# PaPArray_full.net
KiCad netlist of a schematic drawn in EAGLE
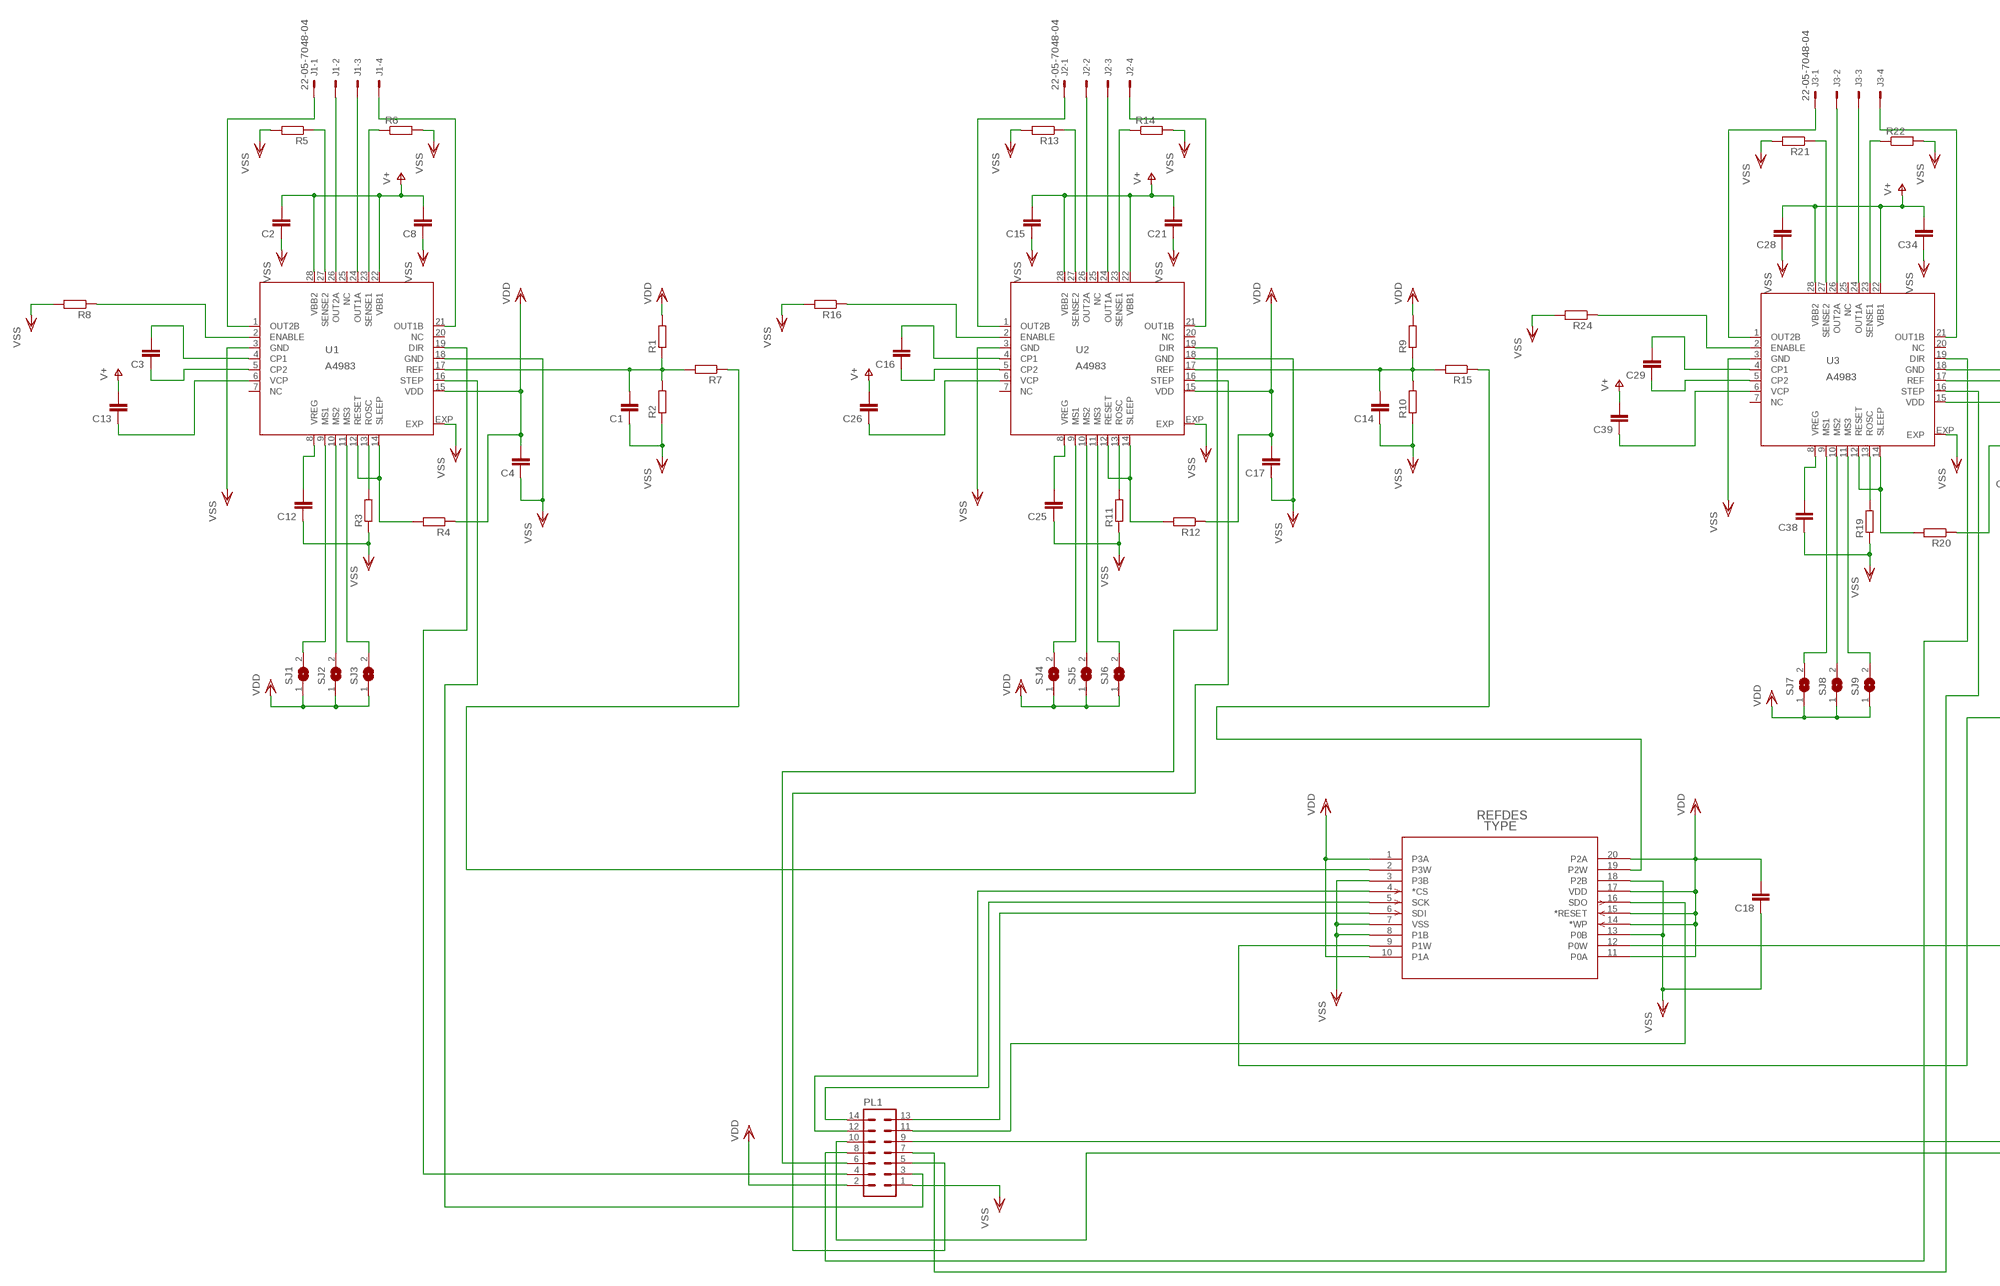
[diagram p0: schematic, sheet 1, part 1 of 2]
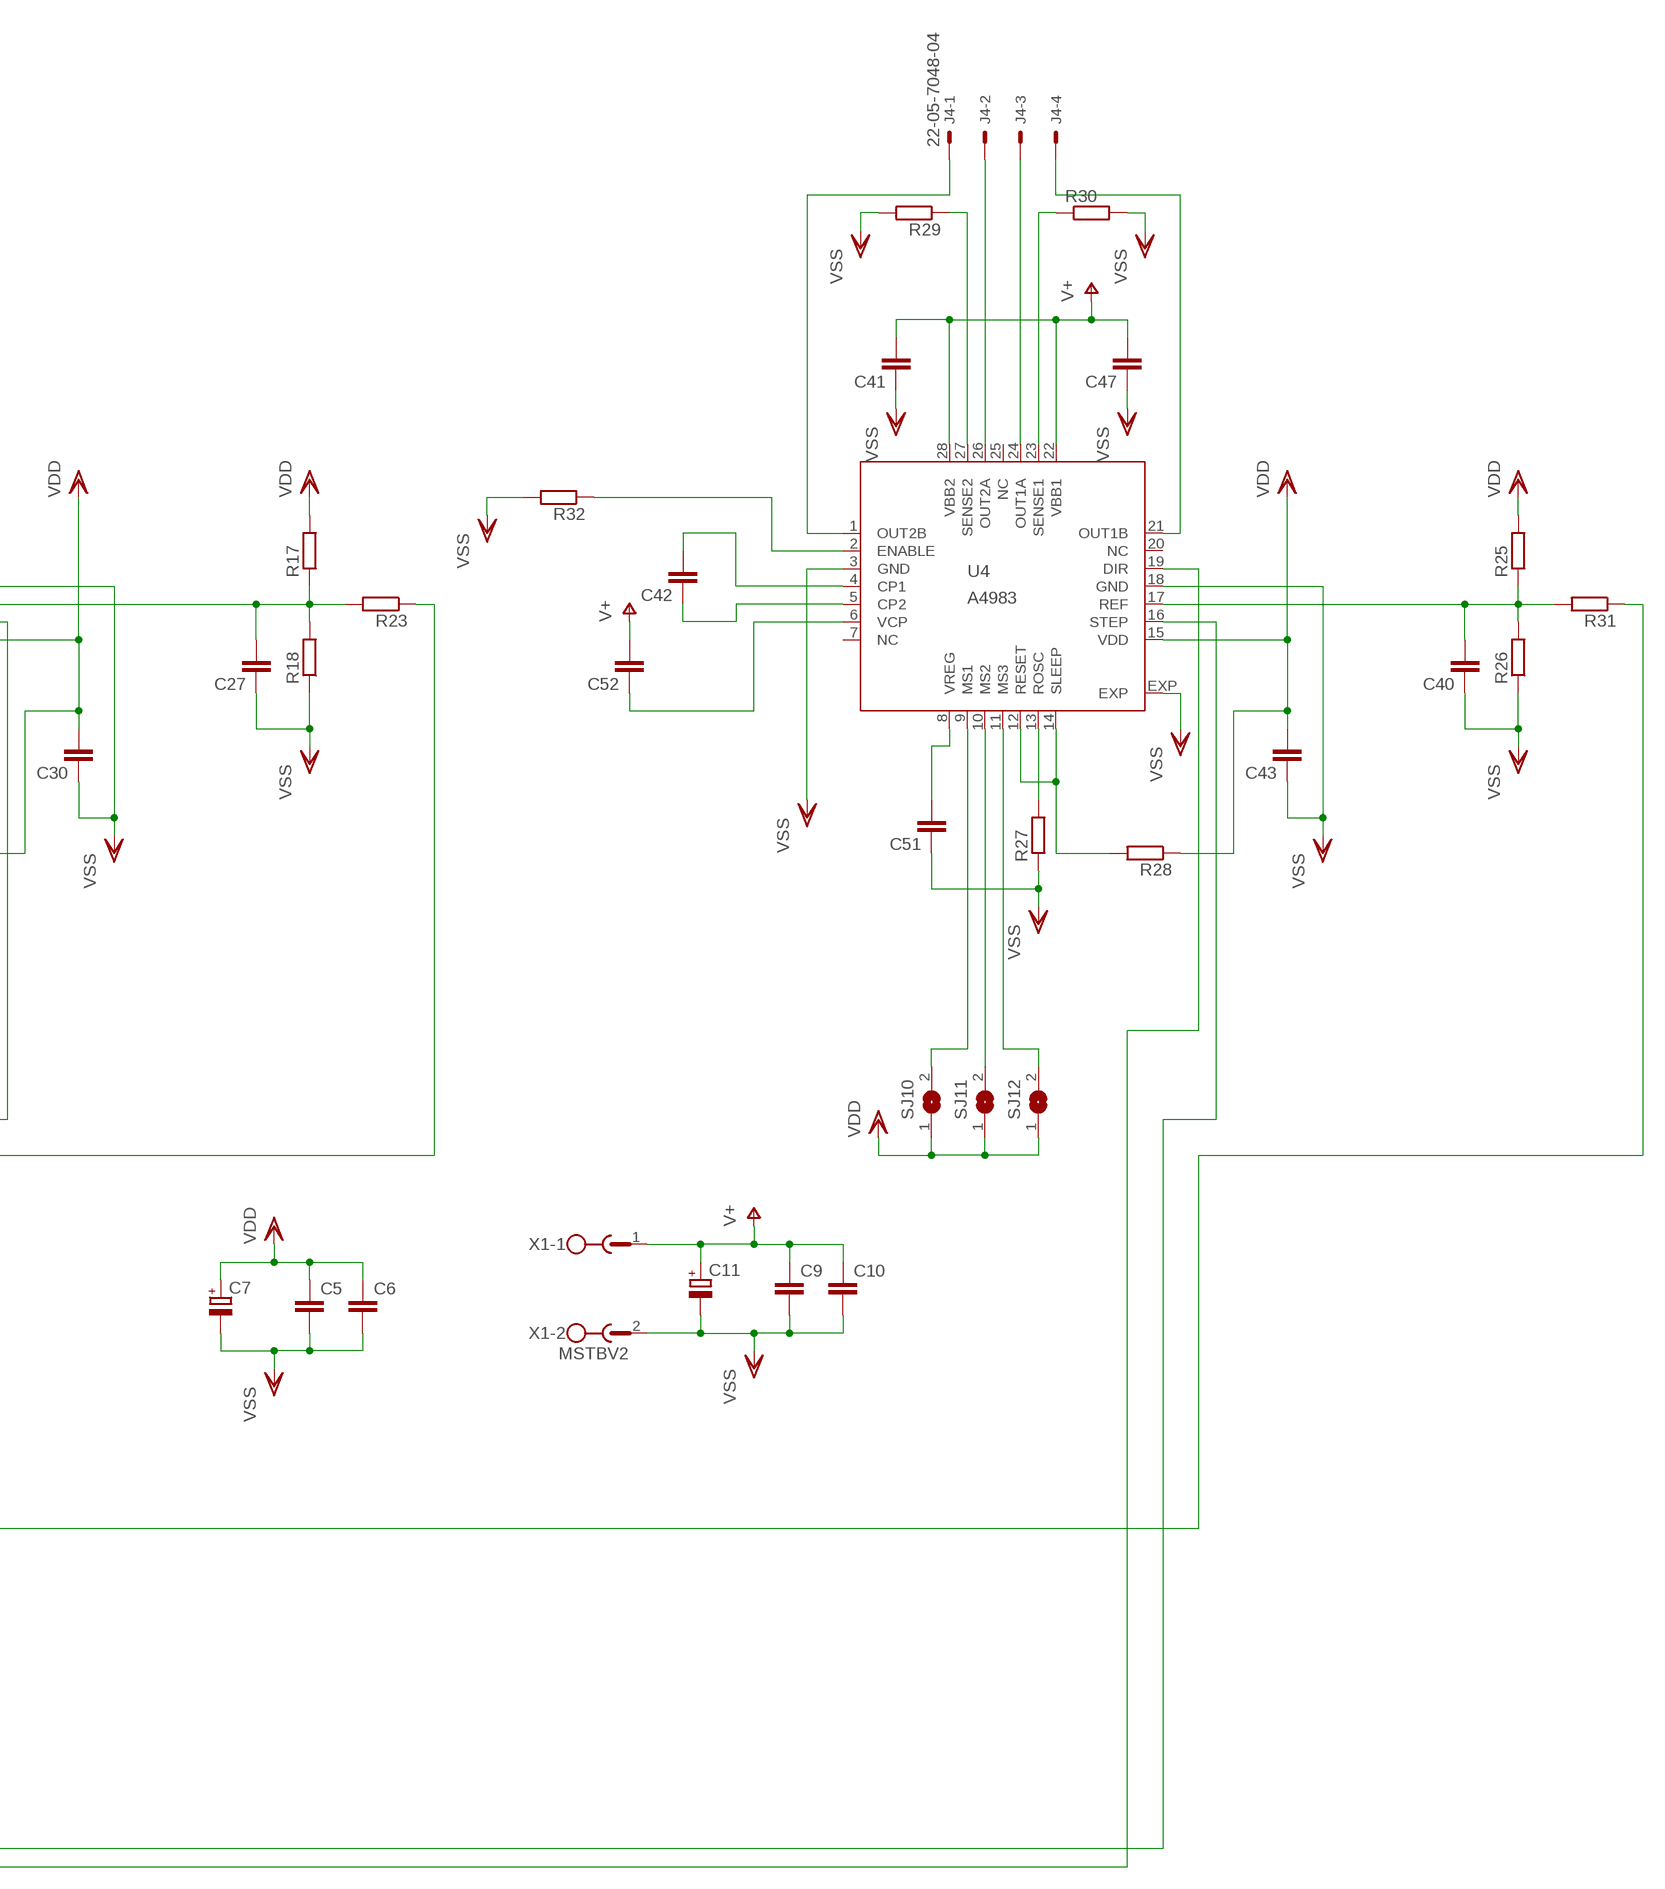
[diagram p1: schematic, sheet 1, part 2 of 2]

(export (version "E")
  (design (tool "Eeschema 10.0.6"))
  (components
    (comp (ref "C1")
      (value "C-EUC0603")
      (footprint "eagle-import:C0603")
      (libsource (lib "eagle-import") (part "C-EUC0603"))
    )
    (comp (ref "C2")
      (value "C-EUC0603")
      (footprint "eagle-import:C0603")
      (libsource (lib "eagle-import") (part "C-EUC0603"))
    )
    (comp (ref "C3")
      (value "C-EUC0603")
      (footprint "eagle-import:C0603")
      (libsource (lib "eagle-import") (part "C-EUC0603"))
    )
    (comp (ref "C4")
      (value "C-EUC0603")
      (footprint "eagle-import:C0603")
      (libsource (lib "eagle-import") (part "C-EUC0603"))
    )
    (comp (ref "C5")
      (value "C-EUC0603")
      (footprint "eagle-import:C0603")
      (libsource (lib "eagle-import") (part "C-EUC0603"))
    )
    (comp (ref "C6")
      (value "C-EUC0603")
      (footprint "eagle-import:C0603")
      (libsource (lib "eagle-import") (part "C-EUC0603"))
    )
    (comp (ref "C7")
      (value "CPOL-EUE5-5")
      (footprint "eagle-import:E5-5")
      (libsource (lib "eagle-import") (part "CPOL-EUE5-5"))
    )
    (comp (ref "C8")
      (value "C-EUC0603")
      (footprint "eagle-import:C0603")
      (libsource (lib "eagle-import") (part "C-EUC0603"))
    )
    (comp (ref "C9")
      (value "C-EUC0603")
      (footprint "eagle-import:C0603")
      (libsource (lib "eagle-import") (part "C-EUC0603"))
    )
    (comp (ref "C10")
      (value "C-EUC0603")
      (footprint "eagle-import:C0603")
      (libsource (lib "eagle-import") (part "C-EUC0603"))
    )
    (comp (ref "C11")
      (value "CPOL-EUE5-5")
      (footprint "eagle-import:E5-5")
      (libsource (lib "eagle-import") (part "CPOL-EUE5-5"))
    )
    (comp (ref "C12")
      (value "C-EUC0603")
      (footprint "eagle-import:C0603")
      (libsource (lib "eagle-import") (part "C-EUC0603"))
    )
    (comp (ref "C13")
      (value "C-EUC0603")
      (footprint "eagle-import:C0603")
      (libsource (lib "eagle-import") (part "C-EUC0603"))
    )
    (comp (ref "C14")
      (value "C-EUC0603")
      (footprint "eagle-import:C0603")
      (libsource (lib "eagle-import") (part "C-EUC0603"))
    )
    (comp (ref "C15")
      (value "C-EUC0603")
      (footprint "eagle-import:C0603")
      (libsource (lib "eagle-import") (part "C-EUC0603"))
    )
    (comp (ref "C16")
      (value "C-EUC0603")
      (footprint "eagle-import:C0603")
      (libsource (lib "eagle-import") (part "C-EUC0603"))
    )
    (comp (ref "C17")
      (value "C-EUC0603")
      (footprint "eagle-import:C0603")
      (libsource (lib "eagle-import") (part "C-EUC0603"))
    )
    (comp (ref "C18")
      (value "C-EUC0603")
      (footprint "eagle-import:C0603")
      (libsource (lib "eagle-import") (part "C-EUC0603"))
    )
    (comp (ref "C21")
      (value "C-EUC0603")
      (footprint "eagle-import:C0603")
      (libsource (lib "eagle-import") (part "C-EUC0603"))
    )
    (comp (ref "C25")
      (value "C-EUC0603")
      (footprint "eagle-import:C0603")
      (libsource (lib "eagle-import") (part "C-EUC0603"))
    )
    (comp (ref "C26")
      (value "C-EUC0603")
      (footprint "eagle-import:C0603")
      (libsource (lib "eagle-import") (part "C-EUC0603"))
    )
    (comp (ref "C27")
      (value "C-EUC0603")
      (footprint "eagle-import:C0603")
      (libsource (lib "eagle-import") (part "C-EUC0603"))
    )
    (comp (ref "C28")
      (value "C-EUC0603")
      (footprint "eagle-import:C0603")
      (libsource (lib "eagle-import") (part "C-EUC0603"))
    )
    (comp (ref "C29")
      (value "C-EUC0603")
      (footprint "eagle-import:C0603")
      (libsource (lib "eagle-import") (part "C-EUC0603"))
    )
    (comp (ref "C30")
      (value "C-EUC0603")
      (footprint "eagle-import:C0603")
      (libsource (lib "eagle-import") (part "C-EUC0603"))
    )
    (comp (ref "C34")
      (value "C-EUC0603")
      (footprint "eagle-import:C0603")
      (libsource (lib "eagle-import") (part "C-EUC0603"))
    )
    (comp (ref "C38")
      (value "C-EUC0603")
      (footprint "eagle-import:C0603")
      (libsource (lib "eagle-import") (part "C-EUC0603"))
    )
    (comp (ref "C39")
      (value "C-EUC0603")
      (footprint "eagle-import:C0603")
      (libsource (lib "eagle-import") (part "C-EUC0603"))
    )
    (comp (ref "C40")
      (value "C-EUC0603")
      (footprint "eagle-import:C0603")
      (libsource (lib "eagle-import") (part "C-EUC0603"))
    )
    (comp (ref "C41")
      (value "C-EUC0603")
      (footprint "eagle-import:C0603")
      (libsource (lib "eagle-import") (part "C-EUC0603"))
    )
    (comp (ref "C42")
      (value "C-EUC0603")
      (footprint "eagle-import:C0603")
      (libsource (lib "eagle-import") (part "C-EUC0603"))
    )
    (comp (ref "C43")
      (value "C-EUC0603")
      (footprint "eagle-import:C0603")
      (libsource (lib "eagle-import") (part "C-EUC0603"))
    )
    (comp (ref "C47")
      (value "C-EUC0603")
      (footprint "eagle-import:C0603")
      (libsource (lib "eagle-import") (part "C-EUC0603"))
    )
    (comp (ref "C51")
      (value "C-EUC0603")
      (footprint "eagle-import:C0603")
      (libsource (lib "eagle-import") (part "C-EUC0603"))
    )
    (comp (ref "C52")
      (value "C-EUC0603")
      (footprint "eagle-import:C0603")
      (libsource (lib "eagle-import") (part "C-EUC0603"))
    )
    (comp (ref "J1")
      (value "22-05-7048-04")
      (footprint "eagle-import:7395-04")
      (libsource (lib "eagle-import") (part "22-?-0405-7048"))
    )
    (comp (ref "J2")
      (value "22-05-7048-04")
      (footprint "eagle-import:7395-04")
      (libsource (lib "eagle-import") (part "22-?-0405-7048"))
    )
    (comp (ref "J3")
      (value "22-05-7048-04")
      (footprint "eagle-import:7395-04")
      (libsource (lib "eagle-import") (part "22-?-0405-7048"))
    )
    (comp (ref "J4")
      (value "22-05-7048-04")
      (footprint "eagle-import:7395-04")
      (libsource (lib "eagle-import") (part "22-?-0405-7048"))
    )
    (comp (ref "PL1")
      (value "14V")
      (footprint "eagle-import:14V")
      (libsource (lib "eagle-import") (part "14V"))
    )
    (comp (ref "R1")
      (value "R-EU_R0805")
      (footprint "eagle-import:R0805")
      (libsource (lib "eagle-import") (part "R-EU_R0805"))
    )
    (comp (ref "R2")
      (value "R-EU_R0805")
      (footprint "eagle-import:R0805")
      (libsource (lib "eagle-import") (part "R-EU_R0805"))
    )
    (comp (ref "R3")
      (value "R-EU_R0805")
      (footprint "eagle-import:R0805")
      (libsource (lib "eagle-import") (part "R-EU_R0805"))
    )
    (comp (ref "R4")
      (value "R-EU_R0805")
      (footprint "eagle-import:R0805")
      (libsource (lib "eagle-import") (part "R-EU_R0805"))
    )
    (comp (ref "R5")
      (value "R-EU_R2512")
      (footprint "eagle-import:R2512")
      (libsource (lib "eagle-import") (part "R-EU_R2512"))
    )
    (comp (ref "R6")
      (value "R-EU_R2512")
      (footprint "eagle-import:R2512")
      (libsource (lib "eagle-import") (part "R-EU_R2512"))
    )
    (comp (ref "R7")
      (value "R-EU_R0805")
      (footprint "eagle-import:R0805")
      (libsource (lib "eagle-import") (part "R-EU_R0805"))
    )
    (comp (ref "R8")
      (value "R-EU_R0805")
      (footprint "eagle-import:R0805")
      (libsource (lib "eagle-import") (part "R-EU_R0805"))
    )
    (comp (ref "R9")
      (value "R-EU_R0805")
      (footprint "eagle-import:R0805")
      (libsource (lib "eagle-import") (part "R-EU_R0805"))
    )
    (comp (ref "R10")
      (value "R-EU_R0805")
      (footprint "eagle-import:R0805")
      (libsource (lib "eagle-import") (part "R-EU_R0805"))
    )
    (comp (ref "R11")
      (value "R-EU_R0805")
      (footprint "eagle-import:R0805")
      (libsource (lib "eagle-import") (part "R-EU_R0805"))
    )
    (comp (ref "R12")
      (value "R-EU_R0805")
      (footprint "eagle-import:R0805")
      (libsource (lib "eagle-import") (part "R-EU_R0805"))
    )
    (comp (ref "R13")
      (value "R-EU_R2512")
      (footprint "eagle-import:R2512")
      (libsource (lib "eagle-import") (part "R-EU_R2512"))
    )
    (comp (ref "R14")
      (value "R-EU_R2512")
      (footprint "eagle-import:R2512")
      (libsource (lib "eagle-import") (part "R-EU_R2512"))
    )
    (comp (ref "R15")
      (value "R-EU_R0805")
      (footprint "eagle-import:R0805")
      (libsource (lib "eagle-import") (part "R-EU_R0805"))
    )
    (comp (ref "R16")
      (value "R-EU_R0805")
      (footprint "eagle-import:R0805")
      (libsource (lib "eagle-import") (part "R-EU_R0805"))
    )
    (comp (ref "R17")
      (value "R-EU_R0805")
      (footprint "eagle-import:R0805")
      (libsource (lib "eagle-import") (part "R-EU_R0805"))
    )
    (comp (ref "R18")
      (value "R-EU_R0805")
      (footprint "eagle-import:R0805")
      (libsource (lib "eagle-import") (part "R-EU_R0805"))
    )
    (comp (ref "R19")
      (value "R-EU_R0805")
      (footprint "eagle-import:R0805")
      (libsource (lib "eagle-import") (part "R-EU_R0805"))
    )
    (comp (ref "R20")
      (value "R-EU_R0805")
      (footprint "eagle-import:R0805")
      (libsource (lib "eagle-import") (part "R-EU_R0805"))
    )
    (comp (ref "R21")
      (value "R-EU_R2512")
      (footprint "eagle-import:R2512")
      (libsource (lib "eagle-import") (part "R-EU_R2512"))
    )
    (comp (ref "R22")
      (value "R-EU_R2512")
      (footprint "eagle-import:R2512")
      (libsource (lib "eagle-import") (part "R-EU_R2512"))
    )
    (comp (ref "R23")
      (value "R-EU_R0805")
      (footprint "eagle-import:R0805")
      (libsource (lib "eagle-import") (part "R-EU_R0805"))
    )
    (comp (ref "R24")
      (value "R-EU_R0805")
      (footprint "eagle-import:R0805")
      (libsource (lib "eagle-import") (part "R-EU_R0805"))
    )
    (comp (ref "R25")
      (value "R-EU_R0805")
      (footprint "eagle-import:R0805")
      (libsource (lib "eagle-import") (part "R-EU_R0805"))
    )
    (comp (ref "R26")
      (value "R-EU_R0805")
      (footprint "eagle-import:R0805")
      (libsource (lib "eagle-import") (part "R-EU_R0805"))
    )
    (comp (ref "R27")
      (value "R-EU_R0805")
      (footprint "eagle-import:R0805")
      (libsource (lib "eagle-import") (part "R-EU_R0805"))
    )
    (comp (ref "R28")
      (value "R-EU_R0805")
      (footprint "eagle-import:R0805")
      (libsource (lib "eagle-import") (part "R-EU_R0805"))
    )
    (comp (ref "R29")
      (value "R-EU_R2512")
      (footprint "eagle-import:R2512")
      (libsource (lib "eagle-import") (part "R-EU_R2512"))
    )
    (comp (ref "R30")
      (value "R-EU_R2512")
      (footprint "eagle-import:R2512")
      (libsource (lib "eagle-import") (part "R-EU_R2512"))
    )
    (comp (ref "R31")
      (value "R-EU_R0805")
      (footprint "eagle-import:R0805")
      (libsource (lib "eagle-import") (part "R-EU_R0805"))
    )
    (comp (ref "R32")
      (value "R-EU_R0805")
      (footprint "eagle-import:R0805")
      (libsource (lib "eagle-import") (part "R-EU_R0805"))
    )
    (comp (ref "SJ1") (value "SJ") (footprint "eagle-import:SJ") (libsource (lib "eagle-import") (part "SJ")))
    (comp (ref "SJ2") (value "SJ") (footprint "eagle-import:SJ") (libsource (lib "eagle-import") (part "SJ")))
    (comp (ref "SJ3") (value "SJ") (footprint "eagle-import:SJ") (libsource (lib "eagle-import") (part "SJ")))
    (comp (ref "SJ4") (value "SJ") (footprint "eagle-import:SJ") (libsource (lib "eagle-import") (part "SJ")))
    (comp (ref "SJ5") (value "SJ") (footprint "eagle-import:SJ") (libsource (lib "eagle-import") (part "SJ")))
    (comp (ref "SJ6") (value "SJ") (footprint "eagle-import:SJ") (libsource (lib "eagle-import") (part "SJ")))
    (comp (ref "SJ7") (value "SJ") (footprint "eagle-import:SJ") (libsource (lib "eagle-import") (part "SJ")))
    (comp (ref "SJ8") (value "SJ") (footprint "eagle-import:SJ") (libsource (lib "eagle-import") (part "SJ")))
    (comp (ref "SJ9") (value "SJ") (footprint "eagle-import:SJ") (libsource (lib "eagle-import") (part "SJ")))
    (comp (ref "SJ10")
      (value "SJ")
      (footprint "eagle-import:SJ")
      (libsource (lib "eagle-import") (part "SJ"))
    )
    (comp (ref "SJ11")
      (value "SJ")
      (footprint "eagle-import:SJ")
      (libsource (lib "eagle-import") (part "SJ"))
    )
    (comp (ref "SJ12")
      (value "SJ")
      (footprint "eagle-import:SJ")
      (libsource (lib "eagle-import") (part "SJ"))
    )
    (comp (ref "U$1")
      (value "MCP4341-XXXX_ST")
      (footprint "eagle-import:TSSOP20_MC")
      (libsource (lib "eagle-import") (part "MCP4341-XXXX_ST"))
    )
    (comp (ref "U1")
      (value "A4983")
      (footprint "eagle-import:QFN28ET")
      (fields (field (name "MPN") "A4983SETTR-T"))
      (libsource (lib "eagle-import") (part "A4983"))
    )
    (comp (ref "U2")
      (value "A4983")
      (footprint "eagle-import:QFN28ET")
      (fields (field (name "MPN") "A4983SETTR-T"))
      (libsource (lib "eagle-import") (part "A4983"))
    )
    (comp (ref "U3")
      (value "A4983")
      (footprint "eagle-import:QFN28ET")
      (fields (field (name "MPN") "A4983SETTR-T"))
      (libsource (lib "eagle-import") (part "A4983"))
    )
    (comp (ref "U4")
      (value "A4983")
      (footprint "eagle-import:QFN28ET")
      (fields (field (name "MPN") "A4983SETTR-T"))
      (libsource (lib "eagle-import") (part "A4983"))
    )
    (comp (ref "X1")
      (value "MSTBV2")
      (footprint "eagle-import:MSTBV2")
      (fields (field (name "MPN") "MSTBV 2,5/2-GF-5.08"))
      (libsource (lib "eagle-import") (part "MSTBV2"))
    )
  )
  (nets
    (net (code "1") (name "Net-(J1A-S)") (class "Default")
      (node (ref "J1") (pin "1") (pinfunction "S_1") (pintype "passive"))
      (node (ref "U1") (pin "1") (pinfunction "OUT2B_1") (pintype "output"))
    )
    (net (code "2") (name "Net-(J1B-S)") (class "Default")
      (node (ref "J1") (pin "2") (pinfunction "S_2") (pintype "passive"))
      (node (ref "U1") (pin "26") (pinfunction "OUT2A_26") (pintype "output"))
    )
    (net (code "3") (name "Net-(J1C-S)") (class "Default")
      (node (ref "J1") (pin "3") (pinfunction "S_3") (pintype "passive"))
      (node (ref "U1") (pin "24") (pinfunction "OUT1A_24") (pintype "output"))
    )
    (net (code "4") (name "Net-(J1D-S)") (class "Default")
      (node (ref "J1") (pin "4") (pinfunction "S_4") (pintype "passive"))
      (node (ref "U1") (pin "21") (pinfunction "OUT1B_21") (pintype "output"))
    )
    (net (code "5") (name "Net-(J2A-S)") (class "Default")
      (node (ref "J2") (pin "1") (pinfunction "S_1") (pintype "passive"))
      (node (ref "U2") (pin "1") (pinfunction "OUT2B_1") (pintype "output"))
    )
    (net (code "6") (name "Net-(J2B-S)") (class "Default")
      (node (ref "J2") (pin "2") (pinfunction "S_2") (pintype "passive"))
      (node (ref "U2") (pin "26") (pinfunction "OUT2A_26") (pintype "output"))
    )
    (net (code "7") (name "Net-(J2C-S)") (class "Default")
      (node (ref "J2") (pin "3") (pinfunction "S_3") (pintype "passive"))
      (node (ref "U2") (pin "24") (pinfunction "OUT1A_24") (pintype "output"))
    )
    (net (code "8") (name "Net-(J2D-S)") (class "Default")
      (node (ref "J2") (pin "4") (pinfunction "S_4") (pintype "passive"))
      (node (ref "U2") (pin "21") (pinfunction "OUT1B_21") (pintype "output"))
    )
    (net (code "9") (name "Net-(J3A-S)") (class "Default")
      (node (ref "J3") (pin "1") (pinfunction "S_1") (pintype "passive"))
      (node (ref "U3") (pin "1") (pinfunction "OUT2B_1") (pintype "output"))
    )
    (net (code "10") (name "Net-(J3B-S)") (class "Default")
      (node (ref "J3") (pin "2") (pinfunction "S_2") (pintype "passive"))
      (node (ref "U3") (pin "26") (pinfunction "OUT2A_26") (pintype "output"))
    )
    (net (code "11") (name "Net-(J3C-S)") (class "Default")
      (node (ref "J3") (pin "3") (pinfunction "S_3") (pintype "passive"))
      (node (ref "U3") (pin "24") (pinfunction "OUT1A_24") (pintype "output"))
    )
    (net (code "12") (name "Net-(J3D-S)") (class "Default")
      (node (ref "J3") (pin "4") (pinfunction "S_4") (pintype "passive"))
      (node (ref "U3") (pin "21") (pinfunction "OUT1B_21") (pintype "output"))
    )
    (net (code "13") (name "Net-(J4A-S)") (class "Default")
      (node (ref "J4") (pin "1") (pinfunction "S_1") (pintype "passive"))
      (node (ref "U4") (pin "1") (pinfunction "OUT2B_1") (pintype "output"))
    )
    (net (code "14") (name "Net-(J4B-S)") (class "Default")
      (node (ref "J4") (pin "2") (pinfunction "S_2") (pintype "passive"))
      (node (ref "U4") (pin "26") (pinfunction "OUT2A_26") (pintype "output"))
    )
    (net (code "15") (name "Net-(J4C-S)") (class "Default")
      (node (ref "J4") (pin "3") (pinfunction "S_3") (pintype "passive"))
      (node (ref "U4") (pin "24") (pinfunction "OUT1A_24") (pintype "output"))
    )
    (net (code "16") (name "Net-(J4D-S)") (class "Default")
      (node (ref "J4") (pin "4") (pinfunction "S_4") (pintype "passive"))
      (node (ref "U4") (pin "21") (pinfunction "OUT1B_21") (pintype "output"))
    )
    (net (code "17") (name "Net-(U$1-*CS)") (class "Default")
      (node (ref "PL1") (pin "12") (pinfunction "12_12") (pintype "passive"))
      (node (ref "U$1") (pin "4") (pinfunction "*CS_4") (pintype "passive"))
    )
    (net (code "18") (name "Net-(U$1-P0W)") (class "Default")
      (node (ref "R31") (pin "1") (pinfunction "1_1") (pintype "passive"))
      (node (ref "U$1") (pin "12") (pinfunction "P0W_12") (pintype "passive"))
    )
    (net (code "19") (name "Net-(U$1-P1W)") (class "Default")
      (node (ref "R23") (pin "1") (pinfunction "1_1") (pintype "passive"))
      (node (ref "U$1") (pin "9") (pinfunction "P1W_9") (pintype "passive"))
    )
    (net (code "20") (name "Net-(U$1-P2W)") (class "Default")
      (node (ref "R15") (pin "1") (pinfunction "1_1") (pintype "passive"))
      (node (ref "U$1") (pin "19") (pinfunction "P2W_19") (pintype "passive"))
    )
    (net (code "21") (name "Net-(U$1-P3W)") (class "Default")
      (node (ref "R7") (pin "1") (pinfunction "1_1") (pintype "passive"))
      (node (ref "U$1") (pin "2") (pinfunction "P3W_2") (pintype "passive"))
    )
    (net (code "22") (name "Net-(U$1-SCK)") (class "Default")
      (node (ref "PL1") (pin "14") (pinfunction "14_14") (pintype "passive"))
      (node (ref "U$1") (pin "5") (pinfunction "SCK_5") (pintype "passive"))
    )
    (net (code "23") (name "Net-(U$1-SDI)") (class "Default")
      (node (ref "PL1") (pin "13") (pinfunction "13_13") (pintype "passive"))
      (node (ref "U$1") (pin "6") (pinfunction "SDI_6") (pintype "passive"))
    )
    (net (code "24") (name "Net-(U$1-SDO)") (class "Default")
      (node (ref "PL1") (pin "11") (pinfunction "11_11") (pintype "passive"))
      (node (ref "U$1") (pin "16") (pinfunction "SDO_16") (pintype "passive"))
    )
    (net (code "25") (name "Net-(U1-CP1)") (class "Default")
      (node (ref "C3") (pin "2") (pinfunction "2_2") (pintype "passive"))
      (node (ref "U1") (pin "4") (pinfunction "CP1_4") (pintype "passive"))
    )
    (net (code "26") (name "Net-(U1-CP2)") (class "Default")
      (node (ref "C3") (pin "1") (pinfunction "1_1") (pintype "passive"))
      (node (ref "U1") (pin "5") (pinfunction "CP2_5") (pintype "passive"))
    )
    (net (code "27") (name "Net-(U1-DIR)") (class "Default")
      (node (ref "PL1") (pin "4") (pinfunction "4_4") (pintype "passive"))
      (node (ref "U1") (pin "19") (pinfunction "DIR_19") (pintype "input"))
    )
    (net (code "28") (name "Net-(U1-ENABLE)") (class "Default")
      (node (ref "R8") (pin "1") (pinfunction "1_1") (pintype "passive"))
      (node (ref "U1") (pin "2") (pinfunction "ENABLE_2") (pintype "input"))
    )
    (net (code "29") (name "Net-(U1-MS1)") (class "Default")
      (node (ref "SJ1") (pin "2") (pinfunction "2_2") (pintype "passive"))
      (node (ref "U1") (pin "9") (pinfunction "MS1_9") (pintype "input"))
    )
    (net (code "30") (name "Net-(U1-MS2)") (class "Default")
      (node (ref "SJ2") (pin "2") (pinfunction "2_2") (pintype "passive"))
      (node (ref "U1") (pin "10") (pinfunction "MS2_10") (pintype "input"))
    )
    (net (code "31") (name "Net-(U1-MS3)") (class "Default")
      (node (ref "SJ3") (pin "2") (pinfunction "2_2") (pintype "passive"))
      (node (ref "U1") (pin "11") (pinfunction "MS3_11") (pintype "input"))
    )
    (net (code "32") (name "Net-(U1-REF)") (class "Default")
      (node (ref "C1") (pin "2") (pinfunction "2_2") (pintype "passive"))
      (node (ref "R1") (pin "1") (pinfunction "1_1") (pintype "passive"))
      (node (ref "R2") (pin "2") (pinfunction "2_2") (pintype "passive"))
      (node (ref "R7") (pin "2") (pinfunction "2_2") (pintype "passive"))
      (node (ref "U1") (pin "17") (pinfunction "REF_17") (pintype "input"))
    )
    (net (code "33") (name "Net-(U1-RESET)") (class "Default")
      (node (ref "R4") (pin "2") (pinfunction "2_2") (pintype "passive"))
      (node (ref "U1") (pin "12") (pinfunction "RESET_12") (pintype "input"))
      (node (ref "U1") (pin "14") (pinfunction "SLEEP_14") (pintype "input"))
    )
    (net (code "34") (name "Net-(U1-ROSC)") (class "Default")
      (node (ref "R3") (pin "2") (pinfunction "2_2") (pintype "passive"))
      (node (ref "U1") (pin "13") (pinfunction "ROSC_13") (pintype "input"))
    )
    (net (code "35") (name "Net-(U1-SENSE1)") (class "Default")
      (node (ref "R6") (pin "1") (pinfunction "1_1") (pintype "passive"))
      (node (ref "U1") (pin "23") (pinfunction "SENSE1_23") (pintype "input"))
    )
    (net (code "36") (name "Net-(U1-SENSE2)") (class "Default")
      (node (ref "R5") (pin "1") (pinfunction "1_1") (pintype "passive"))
      (node (ref "U1") (pin "27") (pinfunction "SENSE2_27") (pintype "input"))
    )
    (net (code "37") (name "Net-(U1-STEP)") (class "Default")
      (node (ref "PL1") (pin "3") (pinfunction "3_3") (pintype "passive"))
      (node (ref "U1") (pin "16") (pinfunction "STEP_16") (pintype "input"))
    )
    (net (code "38") (name "Net-(U1-VCP)") (class "Default")
      (node (ref "C13") (pin "1") (pinfunction "1_1") (pintype "passive"))
      (node (ref "U1") (pin "6") (pinfunction "VCP_6") (pintype "passive"))
    )
    (net (code "39") (name "Net-(U1-VREG)") (class "Default")
      (node (ref "C12") (pin "2") (pinfunction "2_2") (pintype "passive"))
      (node (ref "U1") (pin "8") (pinfunction "VREG_8") (pintype "passive"))
    )
    (net (code "40") (name "Net-(U2-CP1)") (class "Default")
      (node (ref "C16") (pin "2") (pinfunction "2_2") (pintype "passive"))
      (node (ref "U2") (pin "4") (pinfunction "CP1_4") (pintype "passive"))
    )
    (net (code "41") (name "Net-(U2-CP2)") (class "Default")
      (node (ref "C16") (pin "1") (pinfunction "1_1") (pintype "passive"))
      (node (ref "U2") (pin "5") (pinfunction "CP2_5") (pintype "passive"))
    )
    (net (code "42") (name "Net-(U2-DIR)") (class "Default")
      (node (ref "PL1") (pin "6") (pinfunction "6_6") (pintype "passive"))
      (node (ref "U2") (pin "19") (pinfunction "DIR_19") (pintype "input"))
    )
    (net (code "43") (name "Net-(U2-ENABLE)") (class "Default")
      (node (ref "R16") (pin "1") (pinfunction "1_1") (pintype "passive"))
      (node (ref "U2") (pin "2") (pinfunction "ENABLE_2") (pintype "input"))
    )
    (net (code "44") (name "Net-(U2-MS1)") (class "Default")
      (node (ref "SJ4") (pin "2") (pinfunction "2_2") (pintype "passive"))
      (node (ref "U2") (pin "9") (pinfunction "MS1_9") (pintype "input"))
    )
    (net (code "45") (name "Net-(U2-MS2)") (class "Default")
      (node (ref "SJ5") (pin "2") (pinfunction "2_2") (pintype "passive"))
      (node (ref "U2") (pin "10") (pinfunction "MS2_10") (pintype "input"))
    )
    (net (code "46") (name "Net-(U2-MS3)") (class "Default")
      (node (ref "SJ6") (pin "2") (pinfunction "2_2") (pintype "passive"))
      (node (ref "U2") (pin "11") (pinfunction "MS3_11") (pintype "input"))
    )
    (net (code "47") (name "Net-(U2-REF)") (class "Default")
      (node (ref "C14") (pin "2") (pinfunction "2_2") (pintype "passive"))
      (node (ref "R10") (pin "2") (pinfunction "2_2") (pintype "passive"))
      (node (ref "R15") (pin "2") (pinfunction "2_2") (pintype "passive"))
      (node (ref "R9") (pin "1") (pinfunction "1_1") (pintype "passive"))
      (node (ref "U2") (pin "17") (pinfunction "REF_17") (pintype "input"))
    )
    (net (code "48") (name "Net-(U2-RESET)") (class "Default")
      (node (ref "R12") (pin "2") (pinfunction "2_2") (pintype "passive"))
      (node (ref "U2") (pin "12") (pinfunction "RESET_12") (pintype "input"))
      (node (ref "U2") (pin "14") (pinfunction "SLEEP_14") (pintype "input"))
    )
    (net (code "49") (name "Net-(U2-ROSC)") (class "Default")
      (node (ref "R11") (pin "2") (pinfunction "2_2") (pintype "passive"))
      (node (ref "U2") (pin "13") (pinfunction "ROSC_13") (pintype "input"))
    )
    (net (code "50") (name "Net-(U2-SENSE1)") (class "Default")
      (node (ref "R14") (pin "1") (pinfunction "1_1") (pintype "passive"))
      (node (ref "U2") (pin "23") (pinfunction "SENSE1_23") (pintype "input"))
    )
    (net (code "51") (name "Net-(U2-SENSE2)") (class "Default")
      (node (ref "R13") (pin "1") (pinfunction "1_1") (pintype "passive"))
      (node (ref "U2") (pin "27") (pinfunction "SENSE2_27") (pintype "input"))
    )
    (net (code "52") (name "Net-(U2-STEP)") (class "Default")
      (node (ref "PL1") (pin "5") (pinfunction "5_5") (pintype "passive"))
      (node (ref "U2") (pin "16") (pinfunction "STEP_16") (pintype "input"))
    )
    (net (code "53") (name "Net-(U2-VCP)") (class "Default")
      (node (ref "C26") (pin "1") (pinfunction "1_1") (pintype "passive"))
      (node (ref "U2") (pin "6") (pinfunction "VCP_6") (pintype "passive"))
    )
    (net (code "54") (name "Net-(U2-VREG)") (class "Default")
      (node (ref "C25") (pin "2") (pinfunction "2_2") (pintype "passive"))
      (node (ref "U2") (pin "8") (pinfunction "VREG_8") (pintype "passive"))
    )
    (net (code "55") (name "Net-(U3-CP1)") (class "Default")
      (node (ref "C29") (pin "2") (pinfunction "2_2") (pintype "passive"))
      (node (ref "U3") (pin "4") (pinfunction "CP1_4") (pintype "passive"))
    )
    (net (code "56") (name "Net-(U3-CP2)") (class "Default")
      (node (ref "C29") (pin "1") (pinfunction "1_1") (pintype "passive"))
      (node (ref "U3") (pin "5") (pinfunction "CP2_5") (pintype "passive"))
    )
    (net (code "57") (name "Net-(U3-DIR)") (class "Default")
      (node (ref "PL1") (pin "8") (pinfunction "8_8") (pintype "passive"))
      (node (ref "U3") (pin "19") (pinfunction "DIR_19") (pintype "input"))
    )
    (net (code "58") (name "Net-(U3-ENABLE)") (class "Default")
      (node (ref "R24") (pin "1") (pinfunction "1_1") (pintype "passive"))
      (node (ref "U3") (pin "2") (pinfunction "ENABLE_2") (pintype "input"))
    )
    (net (code "59") (name "Net-(U3-MS1)") (class "Default")
      (node (ref "SJ7") (pin "2") (pinfunction "2_2") (pintype "passive"))
      (node (ref "U3") (pin "9") (pinfunction "MS1_9") (pintype "input"))
    )
    (net (code "60") (name "Net-(U3-MS2)") (class "Default")
      (node (ref "SJ8") (pin "2") (pinfunction "2_2") (pintype "passive"))
      (node (ref "U3") (pin "10") (pinfunction "MS2_10") (pintype "input"))
    )
    (net (code "61") (name "Net-(U3-MS3)") (class "Default")
      (node (ref "SJ9") (pin "2") (pinfunction "2_2") (pintype "passive"))
      (node (ref "U3") (pin "11") (pinfunction "MS3_11") (pintype "input"))
    )
    (net (code "62") (name "Net-(U3-REF)") (class "Default")
      (node (ref "C27") (pin "2") (pinfunction "2_2") (pintype "passive"))
      (node (ref "R17") (pin "1") (pinfunction "1_1") (pintype "passive"))
      (node (ref "R18") (pin "2") (pinfunction "2_2") (pintype "passive"))
      (node (ref "R23") (pin "2") (pinfunction "2_2") (pintype "passive"))
      (node (ref "U3") (pin "17") (pinfunction "REF_17") (pintype "input"))
    )
    (net (code "63") (name "Net-(U3-RESET)") (class "Default")
      (node (ref "R20") (pin "2") (pinfunction "2_2") (pintype "passive"))
      (node (ref "U3") (pin "12") (pinfunction "RESET_12") (pintype "input"))
      (node (ref "U3") (pin "14") (pinfunction "SLEEP_14") (pintype "input"))
    )
    (net (code "64") (name "Net-(U3-ROSC)") (class "Default")
      (node (ref "R19") (pin "2") (pinfunction "2_2") (pintype "passive"))
      (node (ref "U3") (pin "13") (pinfunction "ROSC_13") (pintype "input"))
    )
    (net (code "65") (name "Net-(U3-SENSE1)") (class "Default")
      (node (ref "R22") (pin "1") (pinfunction "1_1") (pintype "passive"))
      (node (ref "U3") (pin "23") (pinfunction "SENSE1_23") (pintype "input"))
    )
    (net (code "66") (name "Net-(U3-SENSE2)") (class "Default")
      (node (ref "R21") (pin "1") (pinfunction "1_1") (pintype "passive"))
      (node (ref "U3") (pin "27") (pinfunction "SENSE2_27") (pintype "input"))
    )
    (net (code "67") (name "Net-(U3-STEP)") (class "Default")
      (node (ref "PL1") (pin "7") (pinfunction "7_7") (pintype "passive"))
      (node (ref "U3") (pin "16") (pinfunction "STEP_16") (pintype "input"))
    )
    (net (code "68") (name "Net-(U3-VCP)") (class "Default")
      (node (ref "C39") (pin "1") (pinfunction "1_1") (pintype "passive"))
      (node (ref "U3") (pin "6") (pinfunction "VCP_6") (pintype "passive"))
    )
    (net (code "69") (name "Net-(U3-VREG)") (class "Default")
      (node (ref "C38") (pin "2") (pinfunction "2_2") (pintype "passive"))
      (node (ref "U3") (pin "8") (pinfunction "VREG_8") (pintype "passive"))
    )
    (net (code "70") (name "Net-(U4-CP1)") (class "Default")
      (node (ref "C42") (pin "2") (pinfunction "2_2") (pintype "passive"))
      (node (ref "U4") (pin "4") (pinfunction "CP1_4") (pintype "passive"))
    )
    (net (code "71") (name "Net-(U4-CP2)") (class "Default")
      (node (ref "C42") (pin "1") (pinfunction "1_1") (pintype "passive"))
      (node (ref "U4") (pin "5") (pinfunction "CP2_5") (pintype "passive"))
    )
    (net (code "72") (name "Net-(U4-DIR)") (class "Default")
      (node (ref "PL1") (pin "10") (pinfunction "10_10") (pintype "passive"))
      (node (ref "U4") (pin "19") (pinfunction "DIR_19") (pintype "input"))
    )
    (net (code "73") (name "Net-(U4-ENABLE)") (class "Default")
      (node (ref "R32") (pin "1") (pinfunction "1_1") (pintype "passive"))
      (node (ref "U4") (pin "2") (pinfunction "ENABLE_2") (pintype "input"))
    )
    (net (code "74") (name "Net-(U4-MS1)") (class "Default")
      (node (ref "SJ10") (pin "2") (pinfunction "2_2") (pintype "passive"))
      (node (ref "U4") (pin "9") (pinfunction "MS1_9") (pintype "input"))
    )
    (net (code "75") (name "Net-(U4-MS2)") (class "Default")
      (node (ref "SJ11") (pin "2") (pinfunction "2_2") (pintype "passive"))
      (node (ref "U4") (pin "10") (pinfunction "MS2_10") (pintype "input"))
    )
    (net (code "76") (name "Net-(U4-MS3)") (class "Default")
      (node (ref "SJ12") (pin "2") (pinfunction "2_2") (pintype "passive"))
      (node (ref "U4") (pin "11") (pinfunction "MS3_11") (pintype "input"))
    )
    (net (code "77") (name "Net-(U4-REF)") (class "Default")
      (node (ref "C40") (pin "2") (pinfunction "2_2") (pintype "passive"))
      (node (ref "R25") (pin "1") (pinfunction "1_1") (pintype "passive"))
      (node (ref "R26") (pin "2") (pinfunction "2_2") (pintype "passive"))
      (node (ref "R31") (pin "2") (pinfunction "2_2") (pintype "passive"))
      (node (ref "U4") (pin "17") (pinfunction "REF_17") (pintype "input"))
    )
    (net (code "78") (name "Net-(U4-RESET)") (class "Default")
      (node (ref "R28") (pin "2") (pinfunction "2_2") (pintype "passive"))
      (node (ref "U4") (pin "12") (pinfunction "RESET_12") (pintype "input"))
      (node (ref "U4") (pin "14") (pinfunction "SLEEP_14") (pintype "input"))
    )
    (net (code "79") (name "Net-(U4-ROSC)") (class "Default")
      (node (ref "R27") (pin "2") (pinfunction "2_2") (pintype "passive"))
      (node (ref "U4") (pin "13") (pinfunction "ROSC_13") (pintype "input"))
    )
    (net (code "80") (name "Net-(U4-SENSE1)") (class "Default")
      (node (ref "R30") (pin "1") (pinfunction "1_1") (pintype "passive"))
      (node (ref "U4") (pin "23") (pinfunction "SENSE1_23") (pintype "input"))
    )
    (net (code "81") (name "Net-(U4-SENSE2)") (class "Default")
      (node (ref "R29") (pin "1") (pinfunction "1_1") (pintype "passive"))
      (node (ref "U4") (pin "27") (pinfunction "SENSE2_27") (pintype "input"))
    )
    (net (code "82") (name "Net-(U4-STEP)") (class "Default")
      (node (ref "PL1") (pin "9") (pinfunction "9_9") (pintype "passive"))
      (node (ref "U4") (pin "16") (pinfunction "STEP_16") (pintype "input"))
    )
    (net (code "83") (name "Net-(U4-VCP)") (class "Default")
      (node (ref "C52") (pin "1") (pinfunction "1_1") (pintype "passive"))
      (node (ref "U4") (pin "6") (pinfunction "VCP_6") (pintype "passive"))
    )
    (net (code "84") (name "Net-(U4-VREG)") (class "Default")
      (node (ref "C51") (pin "2") (pinfunction "2_2") (pintype "passive"))
      (node (ref "U4") (pin "8") (pinfunction "VREG_8") (pintype "passive"))
    )
    (net (code "85") (name "V+") (class "Default")
      (node (ref "C10") (pin "1") (pinfunction "1_1") (pintype "passive"))
      (node (ref "C11") (pin "+") (pinfunction "+_+") (pintype "passive"))
      (node (ref "C13") (pin "2") (pinfunction "2_2") (pintype "passive"))
      (node (ref "C15") (pin "2") (pinfunction "2_2") (pintype "passive"))
      (node (ref "C2") (pin "2") (pinfunction "2_2") (pintype "passive"))
      (node (ref "C21") (pin "2") (pinfunction "2_2") (pintype "passive"))
      (node (ref "C26") (pin "2") (pinfunction "2_2") (pintype "passive"))
      (node (ref "C28") (pin "2") (pinfunction "2_2") (pintype "passive"))
      (node (ref "C34") (pin "2") (pinfunction "2_2") (pintype "passive"))
      (node (ref "C39") (pin "2") (pinfunction "2_2") (pintype "passive"))
      (node (ref "C41") (pin "2") (pinfunction "2_2") (pintype "passive"))
      (node (ref "C47") (pin "2") (pinfunction "2_2") (pintype "passive"))
      (node (ref "C52") (pin "2") (pinfunction "2_2") (pintype "passive"))
      (node (ref "C8") (pin "2") (pinfunction "2_2") (pintype "passive"))
      (node (ref "C9") (pin "1") (pinfunction "1_1") (pintype "passive"))
      (node (ref "U1") (pin "22") (pinfunction "VBB1_22") (pintype "power_in"))
      (node (ref "U1") (pin "28") (pinfunction "VBB2_28") (pintype "power_in"))
      (node (ref "U2") (pin "22") (pinfunction "VBB1_22") (pintype "power_in"))
      (node (ref "U2") (pin "28") (pinfunction "VBB2_28") (pintype "power_in"))
      (node (ref "U3") (pin "22") (pinfunction "VBB1_22") (pintype "power_in"))
      (node (ref "U3") (pin "28") (pinfunction "VBB2_28") (pintype "power_in"))
      (node (ref "U4") (pin "22") (pinfunction "VBB1_22") (pintype "power_in"))
      (node (ref "U4") (pin "28") (pinfunction "VBB2_28") (pintype "power_in"))
      (node (ref "X1") (pin "1") (pinfunction "1_1") (pintype "passive"))
    )
    (net (code "86") (name "VDD") (class "Default")
      (node (ref "C17") (pin "2") (pinfunction "2_2") (pintype "passive"))
      (node (ref "C18") (pin "2") (pinfunction "2_2") (pintype "passive"))
      (node (ref "C30") (pin "2") (pinfunction "2_2") (pintype "passive"))
      (node (ref "C4") (pin "2") (pinfunction "2_2") (pintype "passive"))
      (node (ref "C43") (pin "2") (pinfunction "2_2") (pintype "passive"))
      (node (ref "C5") (pin "1") (pinfunction "1_1") (pintype "passive"))
      (node (ref "C6") (pin "1") (pinfunction "1_1") (pintype "passive"))
      (node (ref "C7") (pin "+") (pinfunction "+_+") (pintype "passive"))
      (node (ref "PL1") (pin "2") (pinfunction "2_2") (pintype "passive"))
      (node (ref "R1") (pin "2") (pinfunction "2_2") (pintype "passive"))
      (node (ref "R12") (pin "1") (pinfunction "1_1") (pintype "passive"))
      (node (ref "R17") (pin "2") (pinfunction "2_2") (pintype "passive"))
      (node (ref "R20") (pin "1") (pinfunction "1_1") (pintype "passive"))
      (node (ref "R25") (pin "2") (pinfunction "2_2") (pintype "passive"))
      (node (ref "R28") (pin "1") (pinfunction "1_1") (pintype "passive"))
      (node (ref "R4") (pin "1") (pinfunction "1_1") (pintype "passive"))
      (node (ref "R9") (pin "2") (pinfunction "2_2") (pintype "passive"))
      (node (ref "SJ1") (pin "1") (pinfunction "1_1") (pintype "passive"))
      (node (ref "SJ10") (pin "1") (pinfunction "1_1") (pintype "passive"))
      (node (ref "SJ11") (pin "1") (pinfunction "1_1") (pintype "passive"))
      (node (ref "SJ12") (pin "1") (pinfunction "1_1") (pintype "passive"))
      (node (ref "SJ2") (pin "1") (pinfunction "1_1") (pintype "passive"))
      (node (ref "SJ3") (pin "1") (pinfunction "1_1") (pintype "passive"))
      (node (ref "SJ4") (pin "1") (pinfunction "1_1") (pintype "passive"))
      (node (ref "SJ5") (pin "1") (pinfunction "1_1") (pintype "passive"))
      (node (ref "SJ6") (pin "1") (pinfunction "1_1") (pintype "passive"))
      (node (ref "SJ7") (pin "1") (pinfunction "1_1") (pintype "passive"))
      (node (ref "SJ8") (pin "1") (pinfunction "1_1") (pintype "passive"))
      (node (ref "SJ9") (pin "1") (pinfunction "1_1") (pintype "passive"))
      (node (ref "U$1") (pin "1") (pinfunction "P3A_1") (pintype "passive"))
      (node (ref "U$1") (pin "10") (pinfunction "P1A_10") (pintype "passive"))
      (node (ref "U$1") (pin "11") (pinfunction "P0A_11") (pintype "passive"))
      (node (ref "U$1") (pin "14") (pinfunction "*WP_14") (pintype "passive"))
      (node (ref "U$1") (pin "15") (pinfunction "*RESET_15") (pintype "passive"))
      (node (ref "U$1") (pin "17") (pinfunction "VDD_17") (pintype "passive"))
      (node (ref "U$1") (pin "20") (pinfunction "P2A_20") (pintype "passive"))
      (node (ref "U1") (pin "15") (pinfunction "VDD_15") (pintype "power_in"))
      (node (ref "U2") (pin "15") (pinfunction "VDD_15") (pintype "power_in"))
      (node (ref "U3") (pin "15") (pinfunction "VDD_15") (pintype "power_in"))
      (node (ref "U4") (pin "15") (pinfunction "VDD_15") (pintype "power_in"))
    )
    (net (code "87") (name "VSS") (class "Default")
      (node (ref "C1") (pin "1") (pinfunction "1_1") (pintype "passive"))
      (node (ref "C10") (pin "2") (pinfunction "2_2") (pintype "passive"))
      (node (ref "C11") (pin "-") (pinfunction "-_-") (pintype "passive"))
      (node (ref "C12") (pin "1") (pinfunction "1_1") (pintype "passive"))
      (node (ref "C14") (pin "1") (pinfunction "1_1") (pintype "passive"))
      (node (ref "C15") (pin "1") (pinfunction "1_1") (pintype "passive"))
      (node (ref "C17") (pin "1") (pinfunction "1_1") (pintype "passive"))
      (node (ref "C18") (pin "1") (pinfunction "1_1") (pintype "passive"))
      (node (ref "C2") (pin "1") (pinfunction "1_1") (pintype "passive"))
      (node (ref "C21") (pin "1") (pinfunction "1_1") (pintype "passive"))
      (node (ref "C25") (pin "1") (pinfunction "1_1") (pintype "passive"))
      (node (ref "C27") (pin "1") (pinfunction "1_1") (pintype "passive"))
      (node (ref "C28") (pin "1") (pinfunction "1_1") (pintype "passive"))
      (node (ref "C30") (pin "1") (pinfunction "1_1") (pintype "passive"))
      (node (ref "C34") (pin "1") (pinfunction "1_1") (pintype "passive"))
      (node (ref "C38") (pin "1") (pinfunction "1_1") (pintype "passive"))
      (node (ref "C4") (pin "1") (pinfunction "1_1") (pintype "passive"))
      (node (ref "C40") (pin "1") (pinfunction "1_1") (pintype "passive"))
      (node (ref "C41") (pin "1") (pinfunction "1_1") (pintype "passive"))
      (node (ref "C43") (pin "1") (pinfunction "1_1") (pintype "passive"))
      (node (ref "C47") (pin "1") (pinfunction "1_1") (pintype "passive"))
      (node (ref "C5") (pin "2") (pinfunction "2_2") (pintype "passive"))
      (node (ref "C51") (pin "1") (pinfunction "1_1") (pintype "passive"))
      (node (ref "C6") (pin "2") (pinfunction "2_2") (pintype "passive"))
      (node (ref "C7") (pin "-") (pinfunction "-_-") (pintype "passive"))
      (node (ref "C8") (pin "1") (pinfunction "1_1") (pintype "passive"))
      (node (ref "C9") (pin "2") (pinfunction "2_2") (pintype "passive"))
      (node (ref "PL1") (pin "1") (pinfunction "1_1") (pintype "passive"))
      (node (ref "R10") (pin "1") (pinfunction "1_1") (pintype "passive"))
      (node (ref "R11") (pin "1") (pinfunction "1_1") (pintype "passive"))
      (node (ref "R13") (pin "2") (pinfunction "2_2") (pintype "passive"))
      (node (ref "R14") (pin "2") (pinfunction "2_2") (pintype "passive"))
      (node (ref "R16") (pin "2") (pinfunction "2_2") (pintype "passive"))
      (node (ref "R18") (pin "1") (pinfunction "1_1") (pintype "passive"))
      (node (ref "R19") (pin "1") (pinfunction "1_1") (pintype "passive"))
      (node (ref "R2") (pin "1") (pinfunction "1_1") (pintype "passive"))
      (node (ref "R21") (pin "2") (pinfunction "2_2") (pintype "passive"))
      (node (ref "R22") (pin "2") (pinfunction "2_2") (pintype "passive"))
      (node (ref "R24") (pin "2") (pinfunction "2_2") (pintype "passive"))
      (node (ref "R26") (pin "1") (pinfunction "1_1") (pintype "passive"))
      (node (ref "R27") (pin "1") (pinfunction "1_1") (pintype "passive"))
      (node (ref "R29") (pin "2") (pinfunction "2_2") (pintype "passive"))
      (node (ref "R3") (pin "1") (pinfunction "1_1") (pintype "passive"))
      (node (ref "R30") (pin "2") (pinfunction "2_2") (pintype "passive"))
      (node (ref "R32") (pin "2") (pinfunction "2_2") (pintype "passive"))
      (node (ref "R5") (pin "2") (pinfunction "2_2") (pintype "passive"))
      (node (ref "R6") (pin "2") (pinfunction "2_2") (pintype "passive"))
      (node (ref "R8") (pin "2") (pinfunction "2_2") (pintype "passive"))
      (node (ref "U$1") (pin "13") (pinfunction "P0B_13") (pintype "passive"))
      (node (ref "U$1") (pin "18") (pinfunction "P2B_18") (pintype "passive"))
      (node (ref "U$1") (pin "3") (pinfunction "P3B_3") (pintype "passive"))
      (node (ref "U$1") (pin "7") (pinfunction "VSS_7") (pintype "passive"))
      (node (ref "U$1") (pin "8") (pinfunction "P1B_8") (pintype "passive"))
      (node (ref "U1") (pin "18") (pinfunction "GND_18") (pintype "power_in"))
      (node (ref "U1") (pin "3") (pinfunction "GND_3") (pintype "power_in"))
      (node (ref "U1") (pin "EXP") (pinfunction "EXP_EXP") (pintype "passive"))
      (node (ref "U2") (pin "18") (pinfunction "GND_18") (pintype "power_in"))
      (node (ref "U2") (pin "3") (pinfunction "GND_3") (pintype "power_in"))
      (node (ref "U2") (pin "EXP") (pinfunction "EXP_EXP") (pintype "passive"))
      (node (ref "U3") (pin "18") (pinfunction "GND_18") (pintype "power_in"))
      (node (ref "U3") (pin "3") (pinfunction "GND_3") (pintype "power_in"))
      (node (ref "U3") (pin "EXP") (pinfunction "EXP_EXP") (pintype "passive"))
      (node (ref "U4") (pin "18") (pinfunction "GND_18") (pintype "power_in"))
      (node (ref "U4") (pin "3") (pinfunction "GND_3") (pintype "power_in"))
      (node (ref "U4") (pin "EXP") (pinfunction "EXP_EXP") (pintype "passive"))
      (node (ref "X1") (pin "2") (pinfunction "1_2") (pintype "passive"))
    )
    (net (code "88") (name "unconnected-(U1-NC-Pad7)") (class "Default")
      (node (ref "U1") (pin "7") (pinfunction "NC_7") (pintype "no_connect"))
    )
    (net (code "89") (name "unconnected-(U1-NC-Pad20)") (class "Default")
      (node (ref "U1") (pin "20") (pinfunction "NC_20") (pintype "no_connect"))
    )
    (net (code "90") (name "unconnected-(U1-NC-Pad25)") (class "Default")
      (node (ref "U1") (pin "25") (pinfunction "NC_25") (pintype "no_connect"))
    )
    (net (code "91") (name "unconnected-(U2-NC-Pad7)") (class "Default")
      (node (ref "U2") (pin "7") (pinfunction "NC_7") (pintype "no_connect"))
    )
    (net (code "92") (name "unconnected-(U2-NC-Pad20)") (class "Default")
      (node (ref "U2") (pin "20") (pinfunction "NC_20") (pintype "no_connect"))
    )
    (net (code "93") (name "unconnected-(U2-NC-Pad25)") (class "Default")
      (node (ref "U2") (pin "25") (pinfunction "NC_25") (pintype "no_connect"))
    )
    (net (code "94") (name "unconnected-(U3-NC-Pad7)") (class "Default")
      (node (ref "U3") (pin "7") (pinfunction "NC_7") (pintype "no_connect"))
    )
    (net (code "95") (name "unconnected-(U3-NC-Pad20)") (class "Default")
      (node (ref "U3") (pin "20") (pinfunction "NC_20") (pintype "no_connect"))
    )
    (net (code "96") (name "unconnected-(U3-NC-Pad25)") (class "Default")
      (node (ref "U3") (pin "25") (pinfunction "NC_25") (pintype "no_connect"))
    )
    (net (code "97") (name "unconnected-(U4-NC-Pad7)") (class "Default")
      (node (ref "U4") (pin "7") (pinfunction "NC_7") (pintype "no_connect"))
    )
    (net (code "98") (name "unconnected-(U4-NC-Pad20)") (class "Default")
      (node (ref "U4") (pin "20") (pinfunction "NC_20") (pintype "no_connect"))
    )
    (net (code "99") (name "unconnected-(U4-NC-Pad25)") (class "Default")
      (node (ref "U4") (pin "25") (pinfunction "NC_25") (pintype "no_connect"))
    )
  )
)
